# StaticPlatformMain_v1.net
KiCad netlist of a schematic drawn in EAGLE
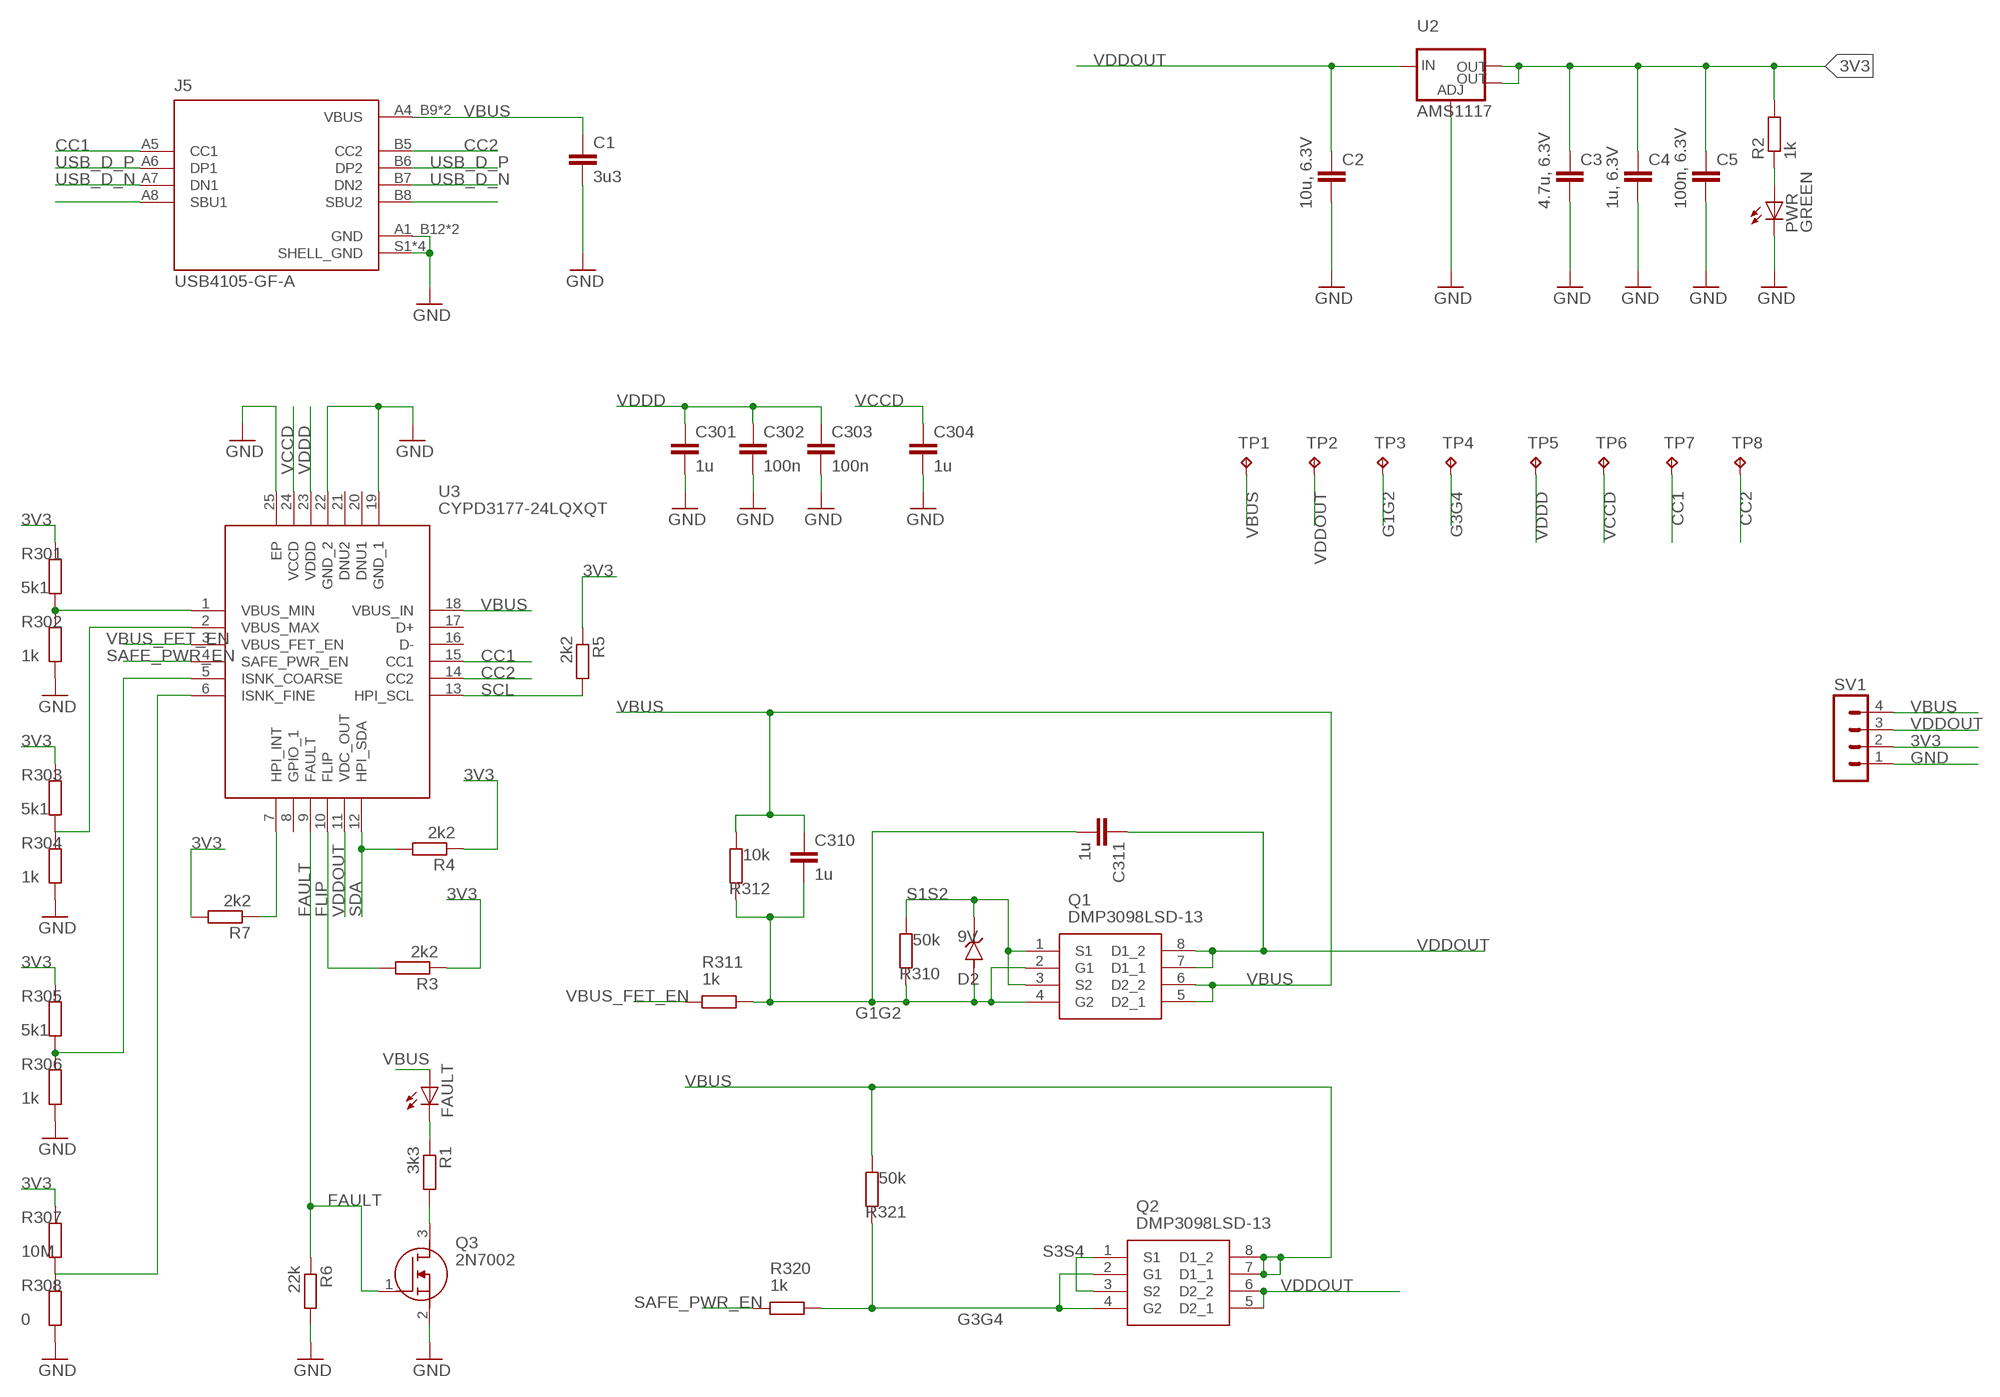
[diagram p0: schematic, sheet 1, part 1 of 2]
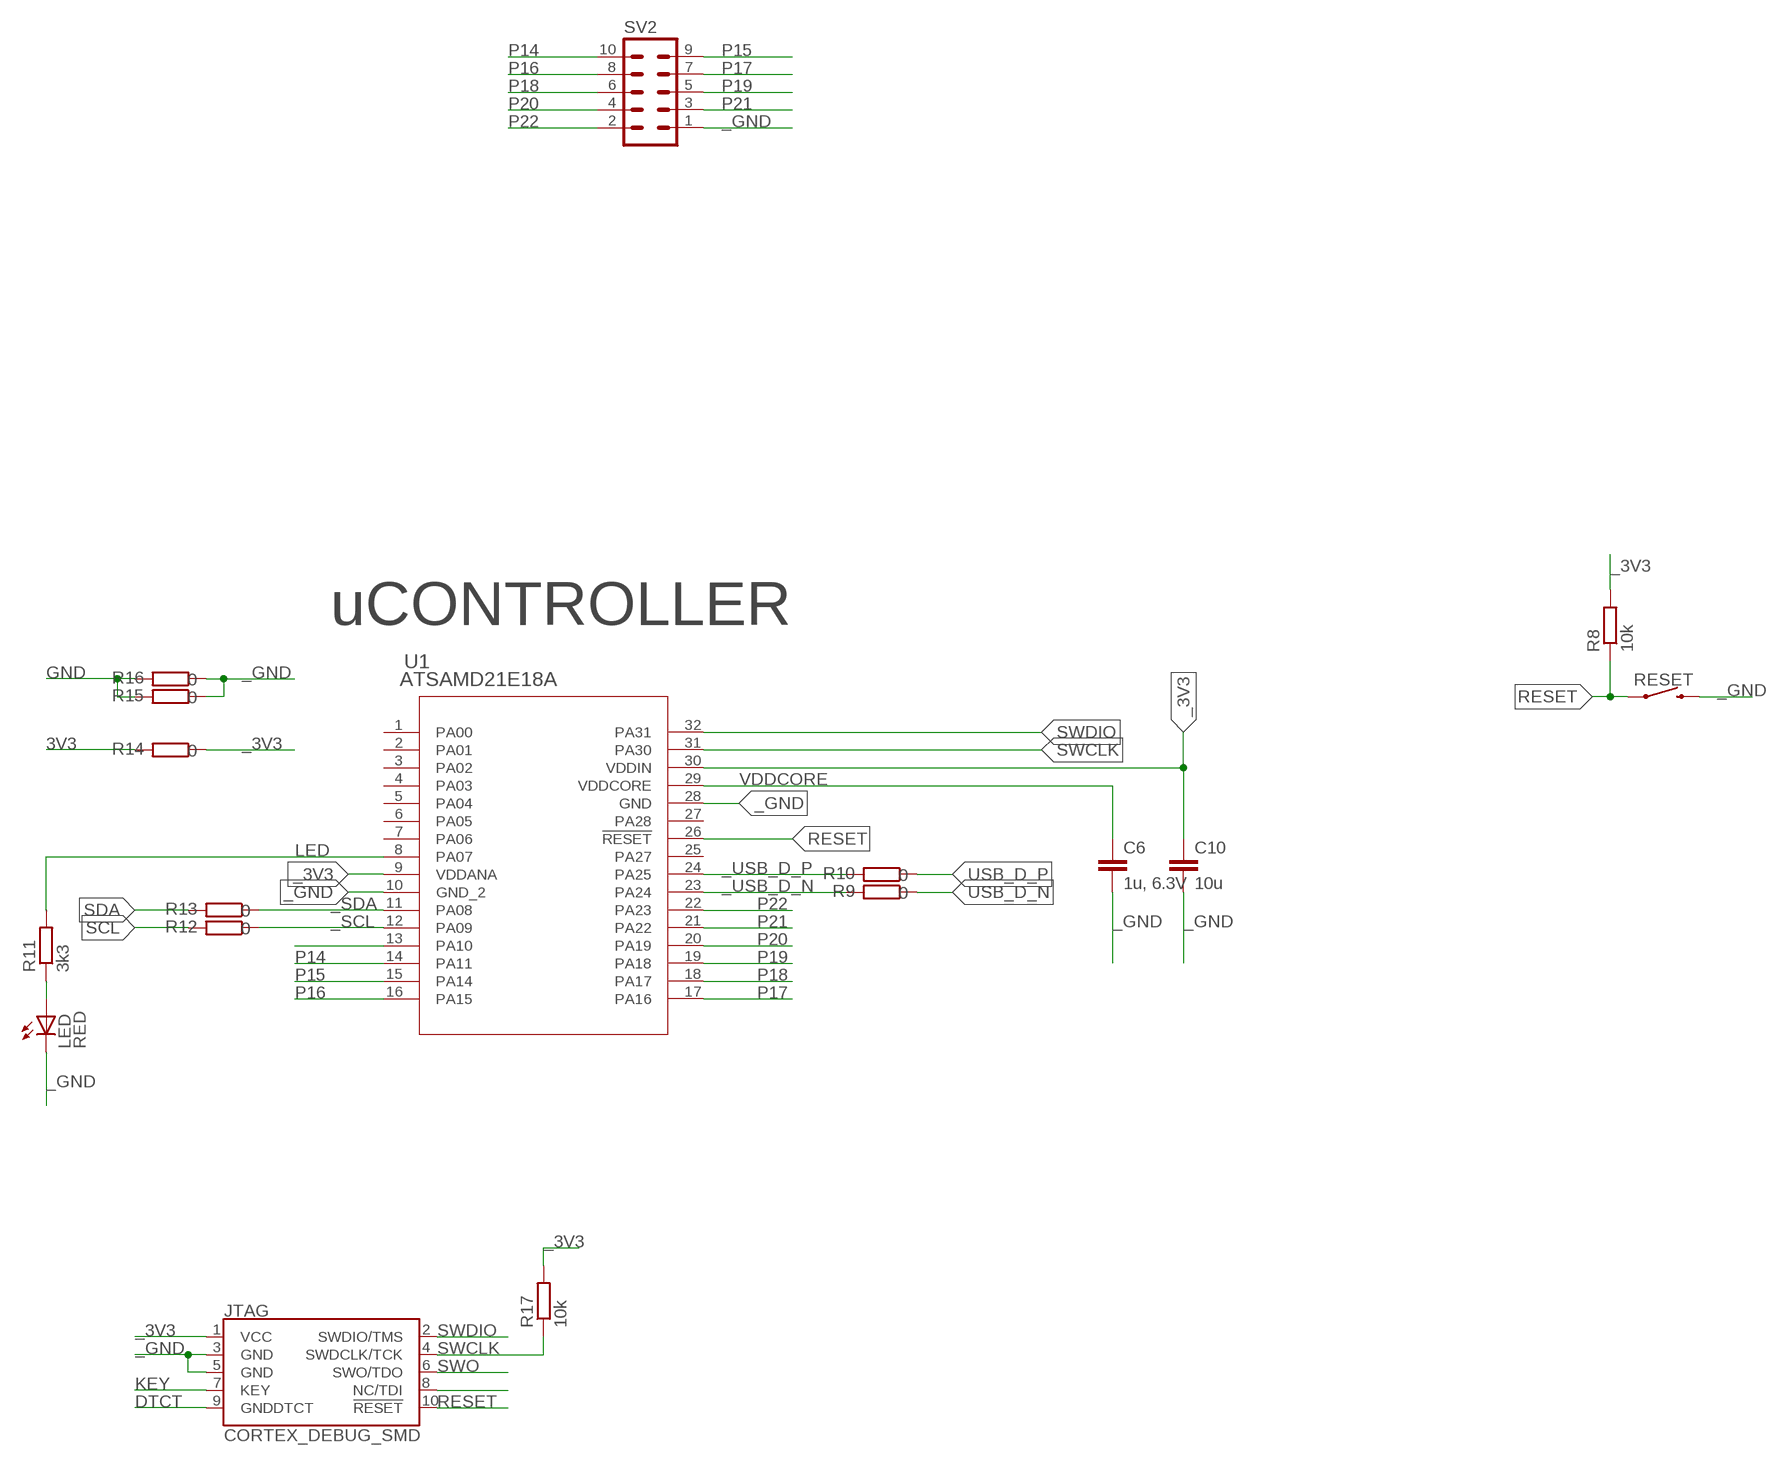
[diagram p1: schematic, sheet 1, part 2 of 2]

(export (version "E")
  (design (tool "Eeschema 10.0.6"))
  (components
    (comp (ref "C1")
      (value "3u3")
      (footprint "eagle-import:C0805K")
      (libsource (lib "eagle-import") (part "C-EUC0805K"))
    )
    (comp (ref "C2")
      (value "10u, 6.3V")
      (footprint "eagle-import:C0805K")
      (libsource (lib "eagle-import") (part "C-EUC0805K"))
    )
    (comp (ref "C3")
      (value "4.7u, 6.3V")
      (footprint "eagle-import:C0805K")
      (libsource (lib "eagle-import") (part "C-EUC0805K"))
    )
    (comp (ref "C4")
      (value "1u, 6.3V")
      (footprint "eagle-import:C0805K")
      (libsource (lib "eagle-import") (part "C-EUC0805K"))
    )
    (comp (ref "C5")
      (value "100n, 6.3V")
      (footprint "eagle-import:C0805K")
      (libsource (lib "eagle-import") (part "C-EUC0805K"))
    )
    (comp (ref "C6")
      (value "1u, 6.3V")
      (footprint "eagle-import:C0805")
      (libsource (lib "eagle-import") (part "C-EUC0805"))
    )
    (comp (ref "C10")
      (value "10u")
      (footprint "eagle-import:C0805")
      (libsource (lib "eagle-import") (part "C-EUC0805"))
    )
    (comp (ref "C301")
      (value "1u")
      (footprint "eagle-import:C0805K")
      (libsource (lib "eagle-import") (part "C-EUC0805K"))
    )
    (comp (ref "C302")
      (value "100n")
      (footprint "eagle-import:C0805K")
      (libsource (lib "eagle-import") (part "C-EUC0805K"))
    )
    (comp (ref "C303")
      (value "100n")
      (footprint "eagle-import:C0805K")
      (libsource (lib "eagle-import") (part "C-EUC0805K"))
    )
    (comp (ref "C304")
      (value "1u")
      (footprint "eagle-import:C0805K")
      (libsource (lib "eagle-import") (part "C-EUC0805K"))
    )
    (comp (ref "C310")
      (value "1u")
      (footprint "eagle-import:C0805K")
      (libsource (lib "eagle-import") (part "C-EUC0805K"))
    )
    (comp (ref "C311")
      (value "1u")
      (footprint "eagle-import:C0805K")
      (libsource (lib "eagle-import") (part "C-EUC0805K"))
    )
    (comp (ref "D2")
      (value "9V")
      (footprint "eagle-import:DIOMELF3515N")
      (fields (field (name "MF") "Taiwan Semiconductor Corporation") (field (name "MP") "BZV55C12 L0G"))
      (libsource (lib "eagle-import") (part "BZV55C12_L0G"))
    )
    (comp (ref "FAULT")
      (value "GREEN")
      (footprint "eagle-import:CHIPLED_0805")
      (libsource (lib "eagle-import") (part "LEDCHIPLED_0805"))
    )
    (comp (ref "J5")
      (value "USB4105-GF-A")
      (footprint "eagle-import:GCT_USB4105-GF-A")
      (fields (field (name "MF") "GCT"))
      (libsource (lib "eagle-import") (part "USB4105-GF-A"))
    )
    (comp (ref "JTAG")
      (value "CORTEX_DEBUG_SMD")
      (footprint "eagle-import:SAMTECH_FTSH-105-01")
      (libsource (lib "eagle-import") (part "CORTEX_DEBUG_SMD"))
    )
    (comp (ref "LED")
      (value "RED")
      (footprint "eagle-import:CHIPLED_0805")
      (libsource (lib "eagle-import") (part "LEDCHIPLED_0805"))
    )
    (comp (ref "PWR")
      (value "GREEN")
      (footprint "eagle-import:CHIPLED_0805")
      (libsource (lib "eagle-import") (part "LEDCHIPLED_0805"))
    )
    (comp (ref "Q1")
      (value "DMP3098LSD-13")
      (footprint "eagle-import:SOIC127P600X175-8N")
      (fields (field (name "MOUSER_PART_NUMBER") "621-DMP3098LSD-13"))
      (libsource (lib "eagle-import") (part "DMP3098LSD-13"))
    )
    (comp (ref "Q2")
      (value "DMP3098LSD-13")
      (footprint "eagle-import:SOIC127P600X175-8N")
      (fields (field (name "MOUSER_PART_NUMBER") "621-DMP3098LSD-13"))
      (libsource (lib "eagle-import") (part "DMP3098LSD-13"))
    )
    (comp (ref "Q3")
      (value "2N7002")
      (footprint "eagle-import:SOT96P240X120-3N")
      (fields (field (name "MOUSER_PART_NUMBER") "512-2N7002"))
      (libsource (lib "eagle-import") (part "2N7002"))
    )
    (comp (ref "R1")
      (value "3k3")
      (footprint "eagle-import:R0805")
      (libsource (lib "eagle-import") (part "R-EU_R0805"))
    )
    (comp (ref "R2")
      (value "1k")
      (footprint "eagle-import:R0805")
      (libsource (lib "eagle-import") (part "R-EU_R0805"))
    )
    (comp (ref "R3")
      (value "2k2")
      (footprint "eagle-import:R0805")
      (libsource (lib "eagle-import") (part "R-EU_R0805"))
    )
    (comp (ref "R4")
      (value "2k2")
      (footprint "eagle-import:R0805")
      (libsource (lib "eagle-import") (part "R-EU_R0805"))
    )
    (comp (ref "R5")
      (value "2k2")
      (footprint "eagle-import:R0805")
      (libsource (lib "eagle-import") (part "R-EU_R0805"))
    )
    (comp (ref "R6")
      (value "22k")
      (footprint "eagle-import:R0805")
      (libsource (lib "eagle-import") (part "R-EU_R0805"))
    )
    (comp (ref "R7")
      (value "2k2")
      (footprint "eagle-import:R0805")
      (libsource (lib "eagle-import") (part "R-EU_R0805"))
    )
    (comp (ref "R8")
      (value "10k")
      (footprint "eagle-import:R0805")
      (libsource (lib "eagle-import") (part "R-EU_R0805"))
    )
    (comp (ref "R9")
      (value "0")
      (footprint "eagle-import:R0805")
      (libsource (lib "eagle-import") (part "R-EU_R0805"))
    )
    (comp (ref "R10")
      (value "0")
      (footprint "eagle-import:R0805")
      (libsource (lib "eagle-import") (part "R-EU_R0805"))
    )
    (comp (ref "R11")
      (value "3k3")
      (footprint "eagle-import:R0805")
      (libsource (lib "eagle-import") (part "R-EU_R0805"))
    )
    (comp (ref "R12")
      (value "0")
      (footprint "eagle-import:R0805")
      (libsource (lib "eagle-import") (part "R-EU_R0805"))
    )
    (comp (ref "R13")
      (value "0")
      (footprint "eagle-import:R0805")
      (libsource (lib "eagle-import") (part "R-EU_R0805"))
    )
    (comp (ref "R14")
      (value "0")
      (footprint "eagle-import:R0805")
      (libsource (lib "eagle-import") (part "R-EU_R0805"))
    )
    (comp (ref "R15")
      (value "0")
      (footprint "eagle-import:R0805")
      (libsource (lib "eagle-import") (part "R-EU_R0805"))
    )
    (comp (ref "R16")
      (value "0")
      (footprint "eagle-import:R0805")
      (libsource (lib "eagle-import") (part "R-EU_R0805"))
    )
    (comp (ref "R17")
      (value "10k")
      (footprint "eagle-import:R0805")
      (libsource (lib "eagle-import") (part "R-EU_R0805"))
    )
    (comp (ref "R301")
      (value "5k1")
      (footprint "eagle-import:R0805")
      (libsource (lib "eagle-import") (part "R-EU_R0805"))
    )
    (comp (ref "R302")
      (value "1k")
      (footprint "eagle-import:R0805")
      (libsource (lib "eagle-import") (part "R-EU_R0805"))
    )
    (comp (ref "R303")
      (value "5k1")
      (footprint "eagle-import:R0805")
      (libsource (lib "eagle-import") (part "R-EU_R0805"))
    )
    (comp (ref "R304")
      (value "1k")
      (footprint "eagle-import:R0805")
      (libsource (lib "eagle-import") (part "R-EU_R0805"))
    )
    (comp (ref "R305")
      (value "5k1")
      (footprint "eagle-import:R0805")
      (libsource (lib "eagle-import") (part "R-EU_R0805"))
    )
    (comp (ref "R306")
      (value "1k")
      (footprint "eagle-import:R0805")
      (libsource (lib "eagle-import") (part "R-EU_R0805"))
    )
    (comp (ref "R307")
      (value "10M")
      (footprint "eagle-import:R0805")
      (libsource (lib "eagle-import") (part "R-EU_R0805"))
    )
    (comp (ref "R308")
      (value "0")
      (footprint "eagle-import:R0805")
      (libsource (lib "eagle-import") (part "R-EU_R0805"))
    )
    (comp (ref "R310")
      (value "50k")
      (footprint "eagle-import:R0805")
      (libsource (lib "eagle-import") (part "R-EU_R0805"))
    )
    (comp (ref "R311")
      (value "1k")
      (footprint "eagle-import:R0805")
      (libsource (lib "eagle-import") (part "R-EU_R0805"))
    )
    (comp (ref "R312")
      (value "10k")
      (footprint "eagle-import:R0805")
      (libsource (lib "eagle-import") (part "R-EU_R0805"))
    )
    (comp (ref "R320")
      (value "1k")
      (footprint "eagle-import:R0805")
      (libsource (lib "eagle-import") (part "R-EU_R0805"))
    )
    (comp (ref "R321")
      (value "50k")
      (footprint "eagle-import:R0805")
      (libsource (lib "eagle-import") (part "R-EU_R0805"))
    )
    (comp (ref "RESET")
      (value "MOMENTARY-SWITCH-SPST-SMD-6.0X3.5MM")
      (footprint "eagle-import:TACTILE_SWITCH_SMD_6.0X3.5MM")
      (libsource (lib "eagle-import") (part "MOMENTARY-SWITCH-SPST-SMD-6.0X3.5MM"))
    )
    (comp (ref "SV1")
      (value "MA04-1")
      (footprint "eagle-import:MA04-1")
      (libsource (lib "eagle-import") (part "MA04-1"))
    )
    (comp (ref "SV2")
      (value "MA05-2")
      (footprint "eagle-import:MA05-2")
      (libsource (lib "eagle-import") (part "MA05-2"))
    )
    (comp (ref "TP1")
      (value "TPTP18R")
      (footprint "eagle-import:TP18R")
      (libsource (lib "eagle-import") (part "TPTP18R"))
    )
    (comp (ref "TP2")
      (value "TPTP18R")
      (footprint "eagle-import:TP18R")
      (libsource (lib "eagle-import") (part "TPTP18R"))
    )
    (comp (ref "TP3")
      (value "TPTP18R")
      (footprint "eagle-import:TP18R")
      (libsource (lib "eagle-import") (part "TPTP18R"))
    )
    (comp (ref "TP4")
      (value "TPTP18R")
      (footprint "eagle-import:TP18R")
      (libsource (lib "eagle-import") (part "TPTP18R"))
    )
    (comp (ref "TP5")
      (value "TPTP18R")
      (footprint "eagle-import:TP18R")
      (libsource (lib "eagle-import") (part "TPTP18R"))
    )
    (comp (ref "TP6")
      (value "TPTP18R")
      (footprint "eagle-import:TP18R")
      (libsource (lib "eagle-import") (part "TPTP18R"))
    )
    (comp (ref "TP7")
      (value "TPTP18R")
      (footprint "eagle-import:TP18R")
      (libsource (lib "eagle-import") (part "TPTP18R"))
    )
    (comp (ref "TP8")
      (value "TPTP18R")
      (footprint "eagle-import:TP18R")
      (libsource (lib "eagle-import") (part "TPTP18R"))
    )
    (comp (ref "U1")
      (value "ATSAMD21E18A")
      (footprint "eagle-import:TQFP32_MC_MCH-M")
      (fields
        (field (name "MANUFACTURER_PART_NUMBER") "ATSAMD21E18A-AU")
        (field (name "COPYRIGHT") "Copyright (C) 2022 Ultra Librarian. All rights reserved.")
      )
      (libsource (lib "eagle-import") (part "ATSAMD21E18A-AUTQFP32_MC_MCH-M"))
    )
    (comp (ref "U2")
      (value "AMS1117")
      (footprint "eagle-import:SOT223")
      (libsource (lib "eagle-import") (part "V_REG_LM1117SOT223"))
    )
    (comp (ref "U3")
      (value "CYPD3177-24LQXQT")
      (footprint "eagle-import:QFN50P400X400X60-25N")
      (fields (field (name "MOUSER_PART_NUMBER") "727-CYPD3177-24LQXQT"))
      (libsource (lib "eagle-import") (part "CYPD3177-24LQXQT"))
    )
  )
  (nets
    (net (code "1") (name "/CC1") (class "Default")
      (node (ref "J5") (pin "A5") (pinfunction "CC1_A5") (pintype "bidirectional"))
      (node (ref "TP7") (pin "TP") (pinfunction "TP_TP") (pintype "input"))
      (node (ref "U3") (pin "15") (pinfunction "CC1_15") (pintype "bidirectional"))
    )
    (net (code "2") (name "/CC2") (class "Default")
      (node (ref "J5") (pin "B5") (pinfunction "CC2_B5") (pintype "bidirectional"))
      (node (ref "TP8") (pin "TP") (pinfunction "TP_TP") (pintype "input"))
      (node (ref "U3") (pin "14") (pinfunction "CC2_14") (pintype "bidirectional"))
    )
    (net (code "3") (name "/DTCT") (class "Default")
      (node (ref "JTAG") (pin "9") (pinfunction "GNDDTCT_9") (pintype "bidirectional"))
    )
    (net (code "4") (name "/FAULT") (class "Default")
      (node (ref "Q3") (pin "1") (pinfunction "G_1") (pintype "bidirectional"))
      (node (ref "R6") (pin "1") (pinfunction "1_1") (pintype "passive"))
      (node (ref "U3") (pin "9") (pinfunction "FAULT_9") (pintype "bidirectional"))
    )
    (net (code "5") (name "/FLIP") (class "Default")
      (node (ref "R3") (pin "2") (pinfunction "2_2") (pintype "passive"))
      (node (ref "U3") (pin "10") (pinfunction "FLIP_10") (pintype "bidirectional"))
    )
    (net (code "6") (name "/G1G2") (class "Default")
      (node (ref "C310") (pin "2") (pinfunction "2_2") (pintype "passive"))
      (node (ref "C311") (pin "2") (pinfunction "2_2") (pintype "passive"))
      (node (ref "D2") (pin "A") (pinfunction "A_A") (pintype "passive"))
      (node (ref "Q1") (pin "2") (pinfunction "G1_2") (pintype "bidirectional"))
      (node (ref "Q1") (pin "4") (pinfunction "G2_4") (pintype "bidirectional"))
      (node (ref "R310") (pin "2") (pinfunction "2_2") (pintype "passive"))
      (node (ref "R311") (pin "1") (pinfunction "1_1") (pintype "passive"))
      (node (ref "R312") (pin "2") (pinfunction "2_2") (pintype "passive"))
      (node (ref "TP3") (pin "TP") (pinfunction "TP_TP") (pintype "input"))
    )
    (net (code "7") (name "/G3G4") (class "Default")
      (node (ref "Q2") (pin "2") (pinfunction "G1_2") (pintype "bidirectional"))
      (node (ref "Q2") (pin "4") (pinfunction "G2_4") (pintype "bidirectional"))
      (node (ref "R320") (pin "1") (pinfunction "1_1") (pintype "passive"))
      (node (ref "R321") (pin "2") (pinfunction "2_2") (pintype "passive"))
      (node (ref "TP4") (pin "TP") (pinfunction "TP_TP") (pintype "input"))
    )
    (net (code "8") (name "/KEY") (class "Default")
      (node (ref "JTAG") (pin "7") (pinfunction "KEY_7") (pintype "bidirectional"))
    )
    (net (code "9") (name "/LED") (class "Default")
      (node (ref "R11") (pin "2") (pinfunction "2_2") (pintype "passive"))
      (node (ref "U1") (pin "8") (pinfunction "PA07_8") (pintype "bidirectional"))
    )
    (net (code "10") (name "/P14") (class "Default")
      (node (ref "SV2") (pin "10") (pinfunction "10_10") (pintype "passive"))
      (node (ref "U1") (pin "14") (pinfunction "PA11_14") (pintype "bidirectional"))
    )
    (net (code "11") (name "/P15") (class "Default")
      (node (ref "SV2") (pin "9") (pinfunction "9_9") (pintype "passive"))
      (node (ref "U1") (pin "15") (pinfunction "PA14_15") (pintype "bidirectional"))
    )
    (net (code "12") (name "/P16") (class "Default")
      (node (ref "SV2") (pin "8") (pinfunction "8_8") (pintype "passive"))
      (node (ref "U1") (pin "16") (pinfunction "PA15_16") (pintype "bidirectional"))
    )
    (net (code "13") (name "/P17") (class "Default")
      (node (ref "SV2") (pin "7") (pinfunction "7_7") (pintype "passive"))
      (node (ref "U1") (pin "17") (pinfunction "PA16_17") (pintype "bidirectional"))
    )
    (net (code "14") (name "/P18") (class "Default")
      (node (ref "SV2") (pin "6") (pinfunction "6_6") (pintype "passive"))
      (node (ref "U1") (pin "18") (pinfunction "PA17_18") (pintype "bidirectional"))
    )
    (net (code "15") (name "/P19") (class "Default")
      (node (ref "SV2") (pin "5") (pinfunction "5_5") (pintype "passive"))
      (node (ref "U1") (pin "19") (pinfunction "PA18_19") (pintype "bidirectional"))
    )
    (net (code "16") (name "/P20") (class "Default")
      (node (ref "SV2") (pin "4") (pinfunction "4_4") (pintype "passive"))
      (node (ref "U1") (pin "20") (pinfunction "PA19_20") (pintype "bidirectional"))
    )
    (net (code "17") (name "/P21") (class "Default")
      (node (ref "SV2") (pin "3") (pinfunction "3_3") (pintype "passive"))
      (node (ref "U1") (pin "21") (pinfunction "PA22_21") (pintype "bidirectional"))
    )
    (net (code "18") (name "/P22") (class "Default")
      (node (ref "SV2") (pin "2") (pinfunction "2_2") (pintype "passive"))
      (node (ref "U1") (pin "22") (pinfunction "PA23_22") (pintype "bidirectional"))
    )
    (net (code "19") (name "/S1S2") (class "Default")
      (node (ref "D2") (pin "C") (pinfunction "K_C") (pintype "passive"))
      (node (ref "Q1") (pin "1") (pinfunction "S1_1") (pintype "bidirectional"))
      (node (ref "Q1") (pin "3") (pinfunction "S2_3") (pintype "bidirectional"))
      (node (ref "R310") (pin "1") (pinfunction "1_1") (pintype "passive"))
    )
    (net (code "20") (name "/S3S4") (class "Default")
      (node (ref "Q2") (pin "1") (pinfunction "S1_1") (pintype "bidirectional"))
      (node (ref "Q2") (pin "3") (pinfunction "S2_3") (pintype "bidirectional"))
    )
    (net (code "21") (name "/SAFE_PWR_EN") (class "Default")
      (node (ref "R320") (pin "2") (pinfunction "2_2") (pintype "passive"))
      (node (ref "U3") (pin "4") (pinfunction "SAFE_PWR_EN_4") (pintype "bidirectional"))
    )
    (net (code "22") (name "/SWO") (class "Default")
      (node (ref "JTAG") (pin "6") (pinfunction "SWO/TDO_6") (pintype "bidirectional"))
    )
    (net (code "23") (name "/VBUS") (class "Default")
      (node (ref "C1") (pin "1") (pinfunction "1_1") (pintype "passive"))
      (node (ref "C310") (pin "1") (pinfunction "1_1") (pintype "passive"))
      (node (ref "FAULT") (pin "A") (pinfunction "A_A") (pintype "passive"))
      (node (ref "J5") (pin "A4_B9") (pinfunction "VBUS_A4_B9") (pintype "power_in"))
      (node (ref "J5") (pin "B4_A9") (pinfunction "VBUS_B4_A9") (pintype "power_in"))
      (node (ref "Q1") (pin "5") (pinfunction "D2_1_5") (pintype "bidirectional"))
      (node (ref "Q1") (pin "6") (pinfunction "D2_2_6") (pintype "bidirectional"))
      (node (ref "Q2") (pin "7") (pinfunction "D1_1_7") (pintype "bidirectional"))
      (node (ref "Q2") (pin "8") (pinfunction "D1_2_8") (pintype "bidirectional"))
      (node (ref "R312") (pin "1") (pinfunction "1_1") (pintype "passive"))
      (node (ref "R321") (pin "1") (pinfunction "1_1") (pintype "passive"))
      (node (ref "SV1") (pin "4") (pinfunction "4_4") (pintype "passive"))
      (node (ref "TP1") (pin "TP") (pinfunction "TP_TP") (pintype "input"))
      (node (ref "U3") (pin "18") (pinfunction "VBUS_IN_18") (pintype "bidirectional"))
    )
    (net (code "24") (name "/VBUS_FET_EN") (class "Default")
      (node (ref "R311") (pin "2") (pinfunction "2_2") (pintype "passive"))
      (node (ref "U3") (pin "3") (pinfunction "VBUS_FET_EN_3") (pintype "bidirectional"))
    )
    (net (code "25") (name "/VCCD") (class "Default")
      (node (ref "C304") (pin "1") (pinfunction "1_1") (pintype "passive"))
      (node (ref "TP6") (pin "TP") (pinfunction "TP_TP") (pintype "input"))
      (node (ref "U3") (pin "24") (pinfunction "VCCD_24") (pintype "bidirectional"))
    )
    (net (code "26") (name "/VDDCORE") (class "Default")
      (node (ref "C6") (pin "1") (pinfunction "1_1") (pintype "passive"))
      (node (ref "U1") (pin "29") (pinfunction "VDDCORE_29") (pintype "power_in"))
    )
    (net (code "27") (name "/VDDD") (class "Default")
      (node (ref "C301") (pin "1") (pinfunction "1_1") (pintype "passive"))
      (node (ref "C302") (pin "1") (pinfunction "1_1") (pintype "passive"))
      (node (ref "C303") (pin "1") (pinfunction "1_1") (pintype "passive"))
      (node (ref "TP5") (pin "TP") (pinfunction "TP_TP") (pintype "input"))
      (node (ref "U3") (pin "23") (pinfunction "VDDD_23") (pintype "bidirectional"))
    )
    (net (code "28") (name "/VDDOUT") (class "Default")
      (node (ref "C2") (pin "1") (pinfunction "1_1") (pintype "passive"))
      (node (ref "C311") (pin "1") (pinfunction "1_1") (pintype "passive"))
      (node (ref "Q1") (pin "7") (pinfunction "D1_1_7") (pintype "bidirectional"))
      (node (ref "Q1") (pin "8") (pinfunction "D1_2_8") (pintype "bidirectional"))
      (node (ref "Q2") (pin "5") (pinfunction "D2_1_5") (pintype "bidirectional"))
      (node (ref "Q2") (pin "6") (pinfunction "D2_2_6") (pintype "bidirectional"))
      (node (ref "SV1") (pin "3") (pinfunction "3_3") (pintype "passive"))
      (node (ref "TP2") (pin "TP") (pinfunction "TP_TP") (pintype "input"))
      (node (ref "U2") (pin "3") (pinfunction "IN_3") (pintype "input"))
      (node (ref "U3") (pin "11") (pinfunction "VDC_OUT_11") (pintype "bidirectional"))
    )
    (net (code "29") (name "/_SCL") (class "Default")
      (node (ref "R12") (pin "1") (pinfunction "1_1") (pintype "passive"))
      (node (ref "U1") (pin "12") (pinfunction "PA09_12") (pintype "bidirectional"))
    )
    (net (code "30") (name "/_SDA") (class "Default")
      (node (ref "R13") (pin "1") (pinfunction "1_1") (pintype "passive"))
      (node (ref "U1") (pin "11") (pinfunction "PA08_11") (pintype "bidirectional"))
    )
    (net (code "31") (name "/_USB_D_N") (class "Default")
      (node (ref "R9") (pin "2") (pinfunction "2_2") (pintype "passive"))
      (node (ref "U1") (pin "23") (pinfunction "PA24_23") (pintype "bidirectional"))
    )
    (net (code "32") (name "/_USB_D_P") (class "Default")
      (node (ref "R10") (pin "2") (pinfunction "2_2") (pintype "passive"))
      (node (ref "U1") (pin "24") (pinfunction "PA25_24") (pintype "bidirectional"))
    )
    (net (code "33") (name "3V3") (class "Default")
      (node (ref "C3") (pin "1") (pinfunction "1_1") (pintype "passive"))
      (node (ref "C4") (pin "1") (pinfunction "1_1") (pintype "passive"))
      (node (ref "C5") (pin "1") (pinfunction "1_1") (pintype "passive"))
      (node (ref "R14") (pin "2") (pinfunction "2_2") (pintype "passive"))
      (node (ref "R2") (pin "2") (pinfunction "2_2") (pintype "passive"))
      (node (ref "R3") (pin "1") (pinfunction "1_1") (pintype "passive"))
      (node (ref "R301") (pin "2") (pinfunction "2_2") (pintype "passive"))
      (node (ref "R303") (pin "2") (pinfunction "2_2") (pintype "passive"))
      (node (ref "R305") (pin "2") (pinfunction "2_2") (pintype "passive"))
      (node (ref "R307") (pin "2") (pinfunction "2_2") (pintype "passive"))
      (node (ref "R4") (pin "1") (pinfunction "1_1") (pintype "passive"))
      (node (ref "R5") (pin "1") (pinfunction "1_1") (pintype "passive"))
      (node (ref "R7") (pin "2") (pinfunction "2_2") (pintype "passive"))
      (node (ref "SV1") (pin "2") (pinfunction "2_2") (pintype "passive"))
      (node (ref "U2") (pin "2") (pinfunction "OUT_2") (pintype "output"))
      (node (ref "U2") (pin "4") (pinfunction "OUT_4") (pintype "output"))
    )
    (net (code "34") (name "GND") (class "Default")
      (node (ref "C1") (pin "2") (pinfunction "2_2") (pintype "passive"))
      (node (ref "C2") (pin "2") (pinfunction "2_2") (pintype "passive"))
      (node (ref "C3") (pin "2") (pinfunction "2_2") (pintype "passive"))
      (node (ref "C301") (pin "2") (pinfunction "2_2") (pintype "passive"))
      (node (ref "C302") (pin "2") (pinfunction "2_2") (pintype "passive"))
      (node (ref "C303") (pin "2") (pinfunction "2_2") (pintype "passive"))
      (node (ref "C304") (pin "2") (pinfunction "2_2") (pintype "passive"))
      (node (ref "C4") (pin "2") (pinfunction "2_2") (pintype "passive"))
      (node (ref "C5") (pin "2") (pinfunction "2_2") (pintype "passive"))
      (node (ref "J5") (pin "A1_B12") (pinfunction "GND_A1_B12") (pintype "power_in"))
      (node (ref "J5") (pin "B1_A12") (pinfunction "GND_B1_A12") (pintype "power_in"))
      (node (ref "J5") (pin "S1") (pinfunction "SHELL_GND_S1") (pintype "power_in"))
      (node (ref "J5") (pin "S2") (pinfunction "SHELL_GND_S2") (pintype "power_in"))
      (node (ref "J5") (pin "S3") (pinfunction "SHELL_GND_S3") (pintype "power_in"))
      (node (ref "J5") (pin "S4") (pinfunction "SHELL_GND_S4") (pintype "power_in"))
      (node (ref "PWR") (pin "C") (pinfunction "C_C") (pintype "passive"))
      (node (ref "Q3") (pin "2") (pinfunction "S_2") (pintype "bidirectional"))
      (node (ref "R15") (pin "2") (pinfunction "2_2") (pintype "passive"))
      (node (ref "R16") (pin "2") (pinfunction "2_2") (pintype "passive"))
      (node (ref "R302") (pin "1") (pinfunction "1_1") (pintype "passive"))
      (node (ref "R304") (pin "1") (pinfunction "1_1") (pintype "passive"))
      (node (ref "R306") (pin "1") (pinfunction "1_1") (pintype "passive"))
      (node (ref "R308") (pin "1") (pinfunction "1_1") (pintype "passive"))
      (node (ref "R6") (pin "2") (pinfunction "2_2") (pintype "passive"))
      (node (ref "SV1") (pin "1") (pinfunction "1_1") (pintype "passive"))
      (node (ref "U2") (pin "1") (pinfunction "ADJ_1") (pintype "input"))
      (node (ref "U3") (pin "19") (pinfunction "GND_1_19") (pintype "bidirectional"))
      (node (ref "U3") (pin "22") (pinfunction "GND_2_22") (pintype "bidirectional"))
      (node (ref "U3") (pin "25") (pinfunction "EP_25") (pintype "bidirectional"))
    )
    (net (code "35") (name "Net-(FAULT-PadC)") (class "Default")
      (node (ref "FAULT") (pin "C") (pinfunction "C_C") (pintype "passive"))
      (node (ref "R1") (pin "1") (pinfunction "1_1") (pintype "passive"))
    )
    (net (code "36") (name "Net-(LED-PadA)") (class "Default")
      (node (ref "LED") (pin "A") (pinfunction "A_A") (pintype "passive"))
      (node (ref "R11") (pin "1") (pinfunction "1_1") (pintype "passive"))
    )
    (net (code "37") (name "Net-(PWR-PadA)") (class "Default")
      (node (ref "PWR") (pin "A") (pinfunction "A_A") (pintype "passive"))
      (node (ref "R2") (pin "1") (pinfunction "1_1") (pintype "passive"))
    )
    (net (code "38") (name "Net-(Q3-D)") (class "Default")
      (node (ref "Q3") (pin "3") (pinfunction "D_3") (pintype "bidirectional"))
      (node (ref "R1") (pin "2") (pinfunction "2_2") (pintype "passive"))
    )
    (net (code "39") (name "Net-(U3-HPI_INT)") (class "Default")
      (node (ref "R7") (pin "1") (pinfunction "1_1") (pintype "passive"))
      (node (ref "U3") (pin "7") (pinfunction "HPI_INT_7") (pintype "bidirectional"))
    )
    (net (code "40") (name "Net-(U3-ISNK_COARSE)") (class "Default")
      (node (ref "R305") (pin "1") (pinfunction "1_1") (pintype "passive"))
      (node (ref "R306") (pin "2") (pinfunction "2_2") (pintype "passive"))
      (node (ref "U3") (pin "5") (pinfunction "ISNK_COARSE_5") (pintype "bidirectional"))
    )
    (net (code "41") (name "Net-(U3-ISNK_FINE)") (class "Default")
      (node (ref "R307") (pin "1") (pinfunction "1_1") (pintype "passive"))
      (node (ref "R308") (pin "2") (pinfunction "2_2") (pintype "passive"))
      (node (ref "U3") (pin "6") (pinfunction "ISNK_FINE_6") (pintype "bidirectional"))
    )
    (net (code "42") (name "Net-(U3-VBUS_MAX)") (class "Default")
      (node (ref "R303") (pin "1") (pinfunction "1_1") (pintype "passive"))
      (node (ref "R304") (pin "2") (pinfunction "2_2") (pintype "passive"))
      (node (ref "U3") (pin "2") (pinfunction "VBUS_MAX_2") (pintype "bidirectional"))
    )
    (net (code "43") (name "Net-(U3-VBUS_MIN)") (class "Default")
      (node (ref "R301") (pin "1") (pinfunction "1_1") (pintype "passive"))
      (node (ref "R302") (pin "2") (pinfunction "2_2") (pintype "passive"))
      (node (ref "U3") (pin "1") (pinfunction "VBUS_MIN_1") (pintype "bidirectional"))
    )
    (net (code "44") (name "RESET") (class "Default")
      (node (ref "JTAG") (pin "10") (pinfunction "~{RESET}_10") (pintype "bidirectional"))
      (node (ref "R8") (pin "1") (pinfunction "1_1") (pintype "passive"))
      (node (ref "RESET") (pin "1") (pinfunction "1_1") (pintype "passive"))
      (node (ref "U1") (pin "26") (pinfunction "~{RESET}_26") (pintype "passive"))
    )
    (net (code "45") (name "SCL") (class "Default")
      (node (ref "R12") (pin "2") (pinfunction "2_2") (pintype "passive"))
      (node (ref "R5") (pin "2") (pinfunction "2_2") (pintype "passive"))
      (node (ref "U3") (pin "13") (pinfunction "HPI_SCL_13") (pintype "bidirectional"))
    )
    (net (code "46") (name "SDA") (class "Default")
      (node (ref "R13") (pin "2") (pinfunction "2_2") (pintype "passive"))
      (node (ref "R4") (pin "2") (pinfunction "2_2") (pintype "passive"))
      (node (ref "U3") (pin "12") (pinfunction "HPI_SDA_12") (pintype "bidirectional"))
    )
    (net (code "47") (name "SWCLK") (class "Default")
      (node (ref "JTAG") (pin "4") (pinfunction "SWDCLK/TCK_4") (pintype "bidirectional"))
      (node (ref "R17") (pin "1") (pinfunction "1_1") (pintype "passive"))
      (node (ref "U1") (pin "31") (pinfunction "PA30_31") (pintype "bidirectional"))
    )
    (net (code "48") (name "SWDIO") (class "Default")
      (node (ref "JTAG") (pin "2") (pinfunction "SWDIO/TMS_2") (pintype "bidirectional"))
      (node (ref "U1") (pin "32") (pinfunction "PA31_32") (pintype "bidirectional"))
    )
    (net (code "49") (name "USB_D_N") (class "Default")
      (node (ref "J5") (pin "A7") (pinfunction "DN1_A7") (pintype "bidirectional"))
      (node (ref "J5") (pin "B7") (pinfunction "DN2_B7") (pintype "bidirectional"))
      (node (ref "R9") (pin "1") (pinfunction "1_1") (pintype "passive"))
    )
    (net (code "50") (name "USB_D_P") (class "Default")
      (node (ref "J5") (pin "A6") (pinfunction "DP1_A6") (pintype "bidirectional"))
      (node (ref "J5") (pin "B6") (pinfunction "DP2_B6") (pintype "bidirectional"))
      (node (ref "R10") (pin "1") (pinfunction "1_1") (pintype "passive"))
    )
    (net (code "51") (name "_3V3") (class "Default")
      (node (ref "C10") (pin "1") (pinfunction "1_1") (pintype "passive"))
      (node (ref "JTAG") (pin "1") (pinfunction "VCC_1") (pintype "bidirectional"))
      (node (ref "R14") (pin "1") (pinfunction "1_1") (pintype "passive"))
      (node (ref "R17") (pin "2") (pinfunction "2_2") (pintype "passive"))
      (node (ref "R8") (pin "2") (pinfunction "2_2") (pintype "passive"))
      (node (ref "U1") (pin "30") (pinfunction "VDDIN_30") (pintype "power_in"))
      (node (ref "U1") (pin "9") (pinfunction "VDDANA_9") (pintype "power_in"))
    )
    (net (code "52") (name "_GND") (class "Default")
      (node (ref "C10") (pin "2") (pinfunction "2_2") (pintype "passive"))
      (node (ref "C6") (pin "2") (pinfunction "2_2") (pintype "passive"))
      (node (ref "JTAG") (pin "3") (pinfunction "GND_3") (pintype "bidirectional"))
      (node (ref "JTAG") (pin "5") (pinfunction "GND_5") (pintype "bidirectional"))
      (node (ref "LED") (pin "C") (pinfunction "C_C") (pintype "passive"))
      (node (ref "R15") (pin "1") (pinfunction "1_1") (pintype "passive"))
      (node (ref "R16") (pin "1") (pinfunction "1_1") (pintype "passive"))
      (node (ref "RESET") (pin "2") (pinfunction "2_2") (pintype "passive"))
      (node (ref "SV2") (pin "1") (pinfunction "1_1") (pintype "passive"))
      (node (ref "U1") (pin "10") (pinfunction "GND_2_10") (pintype "passive"))
      (node (ref "U1") (pin "28") (pinfunction "GND_28") (pintype "passive"))
    )
    (net (code "53") (name "unconnected-(J5-SBU1-PadA8)") (class "Default")
      (node (ref "J5") (pin "A8") (pinfunction "SBU1_A8") (pintype "bidirectional"))
    )
    (net (code "54") (name "unconnected-(J5-SBU2-PadB8)") (class "Default")
      (node (ref "J5") (pin "B8") (pinfunction "SBU2_B8") (pintype "bidirectional"))
    )
    (net (code "55") (name "unconnected-(JTAG-NC{slash}TDI-Pad8)") (class "Default")
      (node (ref "JTAG") (pin "8") (pinfunction "NC/TDI_8") (pintype "bidirectional"))
    )
    (net (code "56") (name "unconnected-(U1-PA00-Pad1)") (class "Default")
      (node (ref "U1") (pin "1") (pinfunction "PA00_1") (pintype "bidirectional"))
    )
    (net (code "57") (name "unconnected-(U1-PA01-Pad2)") (class "Default")
      (node (ref "U1") (pin "2") (pinfunction "PA01_2") (pintype "bidirectional"))
    )
    (net (code "58") (name "unconnected-(U1-PA02-Pad3)") (class "Default")
      (node (ref "U1") (pin "3") (pinfunction "PA02_3") (pintype "bidirectional"))
    )
    (net (code "59") (name "unconnected-(U1-PA03-Pad4)") (class "Default")
      (node (ref "U1") (pin "4") (pinfunction "PA03_4") (pintype "bidirectional"))
    )
    (net (code "60") (name "unconnected-(U1-PA04-Pad5)") (class "Default")
      (node (ref "U1") (pin "5") (pinfunction "PA04_5") (pintype "bidirectional"))
    )
    (net (code "61") (name "unconnected-(U1-PA05-Pad6)") (class "Default")
      (node (ref "U1") (pin "6") (pinfunction "PA05_6") (pintype "bidirectional"))
    )
    (net (code "62") (name "unconnected-(U1-PA06-Pad7)") (class "Default")
      (node (ref "U1") (pin "7") (pinfunction "PA06_7") (pintype "bidirectional"))
    )
    (net (code "63") (name "unconnected-(U1-PA10-Pad13)") (class "Default")
      (node (ref "U1") (pin "13") (pinfunction "PA10_13") (pintype "bidirectional"))
    )
    (net (code "64") (name "unconnected-(U1-PA27-Pad25)") (class "Default")
      (node (ref "U1") (pin "25") (pinfunction "PA27_25") (pintype "bidirectional"))
    )
    (net (code "65") (name "unconnected-(U1-PA28-Pad27)") (class "Default")
      (node (ref "U1") (pin "27") (pinfunction "PA28_27") (pintype "bidirectional"))
    )
    (net (code "66") (name "unconnected-(U3-D+-Pad17)") (class "Default")
      (node (ref "U3") (pin "17") (pinfunction "D+_17") (pintype "bidirectional"))
    )
    (net (code "67") (name "unconnected-(U3-D--Pad16)") (class "Default")
      (node (ref "U3") (pin "16") (pinfunction "D-_16") (pintype "bidirectional"))
    )
    (net (code "68") (name "unconnected-(U3-DNU1-Pad20)") (class "Default")
      (node (ref "U3") (pin "20") (pinfunction "DNU1_20") (pintype "bidirectional"))
    )
    (net (code "69") (name "unconnected-(U3-DNU2-Pad21)") (class "Default")
      (node (ref "U3") (pin "21") (pinfunction "DNU2_21") (pintype "bidirectional"))
    )
    (net (code "70") (name "unconnected-(U3-GPIO_1-Pad8)") (class "Default")
      (node (ref "U3") (pin "8") (pinfunction "GPIO_1_8") (pintype "bidirectional"))
    )
  )
)
